# f-91k.net
KiCad netlist of a schematic drawn in EAGLE
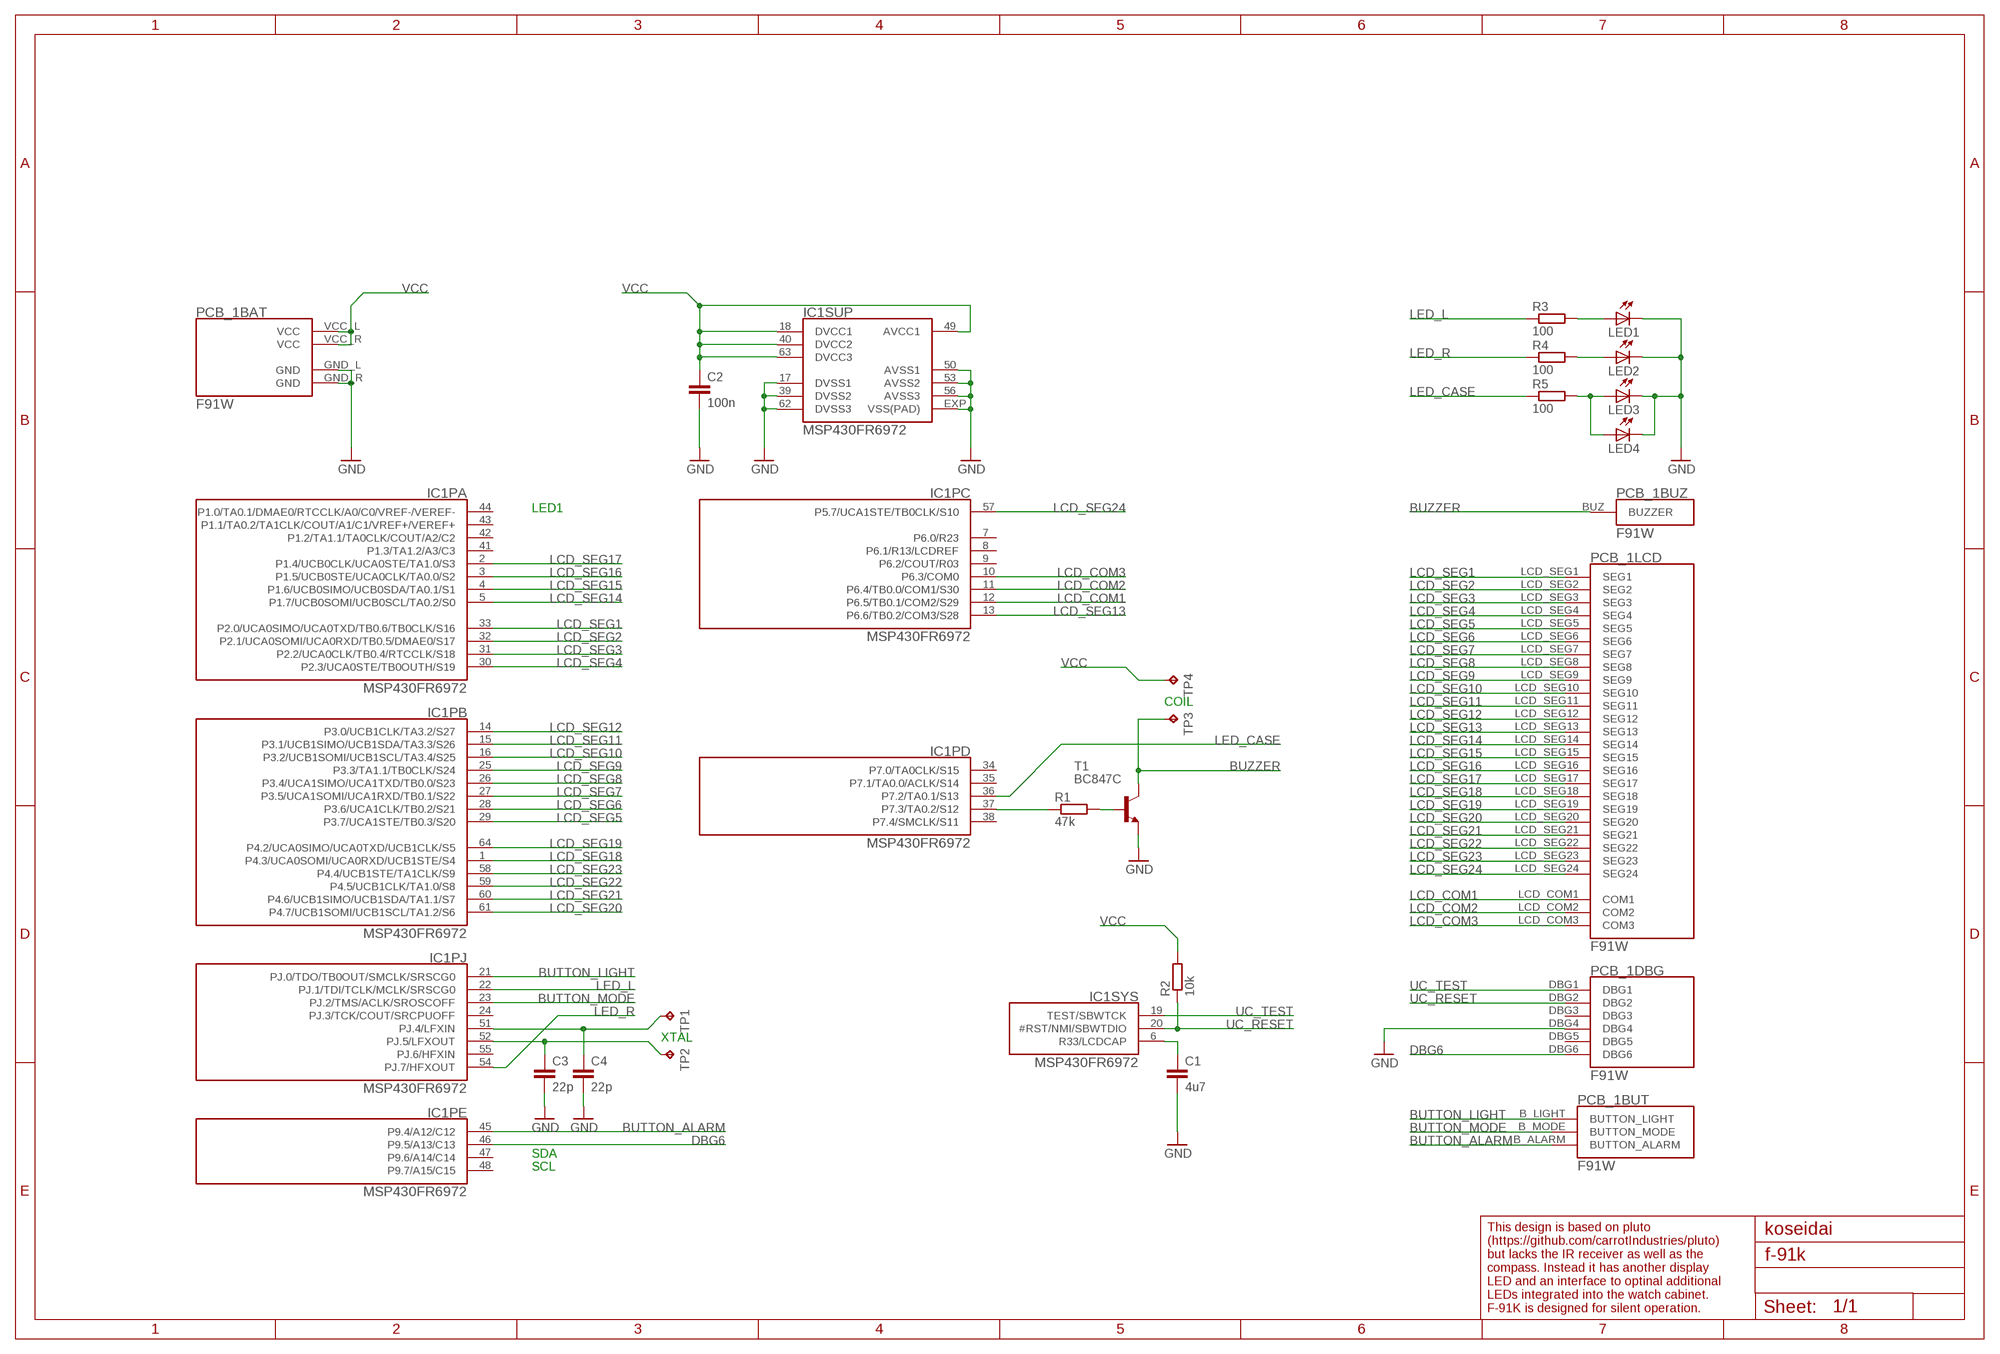
[diagram p0: schematic, sheet 1]

(export (version "E")
  (design (tool "Eeschema 10.0.6"))
  (components
    (comp (ref "C1")
      (value "4u7")
      (footprint "eagle-import:C0603-WW")
      (libsource (lib "eagle-import") (part "C-EUC0603-WW"))
    )
    (comp (ref "C2")
      (value "100n")
      (footprint "eagle-import:C0603-WW")
      (libsource (lib "eagle-import") (part "C-EUC0603-WW"))
    )
    (comp (ref "C3")
      (value "22p")
      (footprint "eagle-import:C0603-WW")
      (libsource (lib "eagle-import") (part "C-EUC0603-WW"))
    )
    (comp (ref "C4")
      (value "22p")
      (footprint "eagle-import:C0603-WW")
      (libsource (lib "eagle-import") (part "C-EUC0603-WW"))
    )
    (comp (ref "IC1")
      (value "MSP430FR6972")
      (footprint "eagle-import:QFN64-9X9")
      (libsource (lib "eagle-import") (part "MSP430FR6972"))
    )
    (comp (ref "LED1")
      (value "LEDCHIPLED_0805")
      (footprint "eagle-import:CHIPLED_0805")
      (libsource (lib "eagle-import") (part "LEDCHIPLED_0805"))
    )
    (comp (ref "LED2")
      (value "LEDCHIPLED_0805")
      (footprint "eagle-import:CHIPLED_0805")
      (libsource (lib "eagle-import") (part "LEDCHIPLED_0805"))
    )
    (comp (ref "LED3")
      (value "LEDCHIPLED_0603")
      (footprint "eagle-import:CHIPLED_0603")
      (libsource (lib "eagle-import") (part "LEDCHIPLED_0603"))
    )
    (comp (ref "LED4")
      (value "LEDCHIPLED_0603")
      (footprint "eagle-import:CHIPLED_0603")
      (libsource (lib "eagle-import") (part "LEDCHIPLED_0603"))
    )
    (comp (ref "PCB_1")
      (value "F91W")
      (footprint "eagle-import:F91W")
      (libsource (lib "eagle-import") (part "F91W"))
    )
    (comp (ref "R1")
      (value "47k")
      (footprint "eagle-import:R0603-WW")
      (libsource (lib "eagle-import") (part "R-EU_R0603-WW"))
    )
    (comp (ref "R2")
      (value "10k")
      (footprint "eagle-import:R0603-WW")
      (libsource (lib "eagle-import") (part "R-EU_R0603-WW"))
    )
    (comp (ref "R3")
      (value "100")
      (footprint "eagle-import:R0603-WW")
      (libsource (lib "eagle-import") (part "R-EU_R0603-WW"))
    )
    (comp (ref "R4")
      (value "100")
      (footprint "eagle-import:R0603-WW")
      (libsource (lib "eagle-import") (part "R-EU_R0603-WW"))
    )
    (comp (ref "R5")
      (value "100")
      (footprint "eagle-import:R0603-WW")
      (libsource (lib "eagle-import") (part "R-EU_R0603-WW"))
    )
    (comp (ref "T1")
      (value "BC847C")
      (footprint "eagle-import:SOT23-BEC")
      (libsource (lib "eagle-import") (part "-NPN-SOT23-BECBC847C"))
    )
    (comp (ref "TP1")
      (value "TPTP07SQ")
      (footprint "eagle-import:TP07SQ")
      (libsource (lib "eagle-import") (part "TPTP07SQ"))
    )
    (comp (ref "TP2")
      (value "TPTP07SQ")
      (footprint "eagle-import:TP07SQ")
      (libsource (lib "eagle-import") (part "TPTP07SQ"))
    )
    (comp (ref "TP3")
      (value "TPTP11SQ")
      (footprint "eagle-import:TP11SQ")
      (libsource (lib "eagle-import") (part "TPTP11SQ"))
    )
    (comp (ref "TP4")
      (value "TPTP11SQ")
      (footprint "eagle-import:TP11SQ")
      (libsource (lib "eagle-import") (part "TPTP11SQ"))
    )
  )
  (nets
    (net (code "1") (name "/BUTTON_ALARM") (class "Default")
      (node (ref "IC1") (pin "45") (pinfunction "P9.4/A12/C12_45") (pintype "bidirectional"))
      (node (ref "PCB_1") (pin "B_ALARM") (pinfunction "BUTTON_ALARM_B_ALARM") (pintype "output"))
    )
    (net (code "2") (name "/BUTTON_LIGHT") (class "Default")
      (node (ref "IC1") (pin "21") (pinfunction "PJ.0/TDO/TB0OUT/SMCLK/SRSCG0_21") (pintype "bidirectional"))
      (node (ref "PCB_1") (pin "B_LIGHT") (pinfunction "BUTTON_LIGHT_B_LIGHT") (pintype "output"))
    )
    (net (code "3") (name "/BUTTON_MODE") (class "Default")
      (node (ref "IC1") (pin "23") (pinfunction "PJ.2/TMS/ACLK/SROSCOFF_23") (pintype "bidirectional"))
      (node (ref "PCB_1") (pin "B_MODE") (pinfunction "BUTTON_MODE_B_MODE") (pintype "output"))
    )
    (net (code "4") (name "/BUZZER") (class "Default")
      (node (ref "PCB_1") (pin "BUZ") (pinfunction "BUZZER_BUZ") (pintype "passive"))
      (node (ref "T1") (pin "C") (pinfunction "C_C") (pintype "passive"))
      (node (ref "TP3") (pin "TP") (pinfunction "TP_TP") (pintype "input"))
    )
    (net (code "5") (name "/DBG6") (class "Default")
      (node (ref "IC1") (pin "46") (pinfunction "P9.5/A13/C13_46") (pintype "bidirectional"))
      (node (ref "PCB_1") (pin "DBG6") (pinfunction "DBG6_DBG6") (pintype "bidirectional"))
    )
    (net (code "6") (name "/LCD_COM1") (class "Default")
      (node (ref "IC1") (pin "12") (pinfunction "P6.5/TB0.1/COM2/S29_12") (pintype "bidirectional"))
      (node (ref "PCB_1") (pin "LCD_COM1") (pinfunction "COM1_LCD_COM1") (pintype "input"))
    )
    (net (code "7") (name "/LCD_COM2") (class "Default")
      (node (ref "IC1") (pin "11") (pinfunction "P6.4/TB0.0/COM1/S30_11") (pintype "bidirectional"))
      (node (ref "PCB_1") (pin "LCD_COM2") (pinfunction "COM2_LCD_COM2") (pintype "input"))
    )
    (net (code "8") (name "/LCD_COM3") (class "Default")
      (node (ref "IC1") (pin "10") (pinfunction "P6.3/COM0_10") (pintype "bidirectional"))
      (node (ref "PCB_1") (pin "LCD_COM3") (pinfunction "COM3_LCD_COM3") (pintype "input"))
    )
    (net (code "9") (name "/LCD_SEG1") (class "Default")
      (node (ref "IC1") (pin "33") (pinfunction "P2.0/UCA0SIMO/UCA0TXD/TB0.6/TB0CLK/S16_33") (pintype "bidirectional"))
      (node (ref "PCB_1") (pin "LCD_SEG1") (pinfunction "SEG1_LCD_SEG1") (pintype "input"))
    )
    (net (code "10") (name "/LCD_SEG2") (class "Default")
      (node (ref "IC1") (pin "32") (pinfunction "P2.1/UCA0SOMI/UCA0RXD/TB0.5/DMAE0/S17_32") (pintype "bidirectional"))
      (node (ref "PCB_1") (pin "LCD_SEG2") (pinfunction "SEG2_LCD_SEG2") (pintype "input"))
    )
    (net (code "11") (name "/LCD_SEG3") (class "Default")
      (node (ref "IC1") (pin "31") (pinfunction "P2.2/UCA0CLK/TB0.4/RTCCLK/S18_31") (pintype "bidirectional"))
      (node (ref "PCB_1") (pin "LCD_SEG3") (pinfunction "SEG3_LCD_SEG3") (pintype "input"))
    )
    (net (code "12") (name "/LCD_SEG4") (class "Default")
      (node (ref "IC1") (pin "30") (pinfunction "P2.3/UCA0STE/TB0OUTH/S19_30") (pintype "bidirectional"))
      (node (ref "PCB_1") (pin "LCD_SEG4") (pinfunction "SEG4_LCD_SEG4") (pintype "input"))
    )
    (net (code "13") (name "/LCD_SEG5") (class "Default")
      (node (ref "IC1") (pin "29") (pinfunction "P3.7/UCA1STE/TB0.3/S20_29") (pintype "bidirectional"))
      (node (ref "PCB_1") (pin "LCD_SEG5") (pinfunction "SEG5_LCD_SEG5") (pintype "input"))
    )
    (net (code "14") (name "/LCD_SEG6") (class "Default")
      (node (ref "IC1") (pin "28") (pinfunction "P3.6/UCA1CLK/TB0.2/S21_28") (pintype "bidirectional"))
      (node (ref "PCB_1") (pin "LCD_SEG6") (pinfunction "SEG6_LCD_SEG6") (pintype "input"))
    )
    (net (code "15") (name "/LCD_SEG7") (class "Default")
      (node (ref "IC1") (pin "27") (pinfunction "P3.5/UCA1SOMI/UCA1RXD/TB0.1/S22_27") (pintype "bidirectional"))
      (node (ref "PCB_1") (pin "LCD_SEG7") (pinfunction "SEG7_LCD_SEG7") (pintype "input"))
    )
    (net (code "16") (name "/LCD_SEG8") (class "Default")
      (node (ref "IC1") (pin "26") (pinfunction "P3.4/UCA1SIMO/UCA1TXD/TB0.0/S23_26") (pintype "bidirectional"))
      (node (ref "PCB_1") (pin "LCD_SEG8") (pinfunction "SEG8_LCD_SEG8") (pintype "input"))
    )
    (net (code "17") (name "/LCD_SEG9") (class "Default")
      (node (ref "IC1") (pin "25") (pinfunction "P3.3/TA1.1/TB0CLK/S24_25") (pintype "bidirectional"))
      (node (ref "PCB_1") (pin "LCD_SEG9") (pinfunction "SEG9_LCD_SEG9") (pintype "input"))
    )
    (net (code "18") (name "/LCD_SEG10") (class "Default")
      (node (ref "IC1") (pin "16") (pinfunction "P3.2/UCB1SOMI/UCB1SCL/TA3.4/S25_16") (pintype "bidirectional"))
      (node (ref "PCB_1") (pin "LCD_SEG10") (pinfunction "SEG10_LCD_SEG10") (pintype "input"))
    )
    (net (code "19") (name "/LCD_SEG11") (class "Default")
      (node (ref "IC1") (pin "15") (pinfunction "P3.1/UCB1SIMO/UCB1SDA/TA3.3/S26_15") (pintype "bidirectional"))
      (node (ref "PCB_1") (pin "LCD_SEG11") (pinfunction "SEG11_LCD_SEG11") (pintype "input"))
    )
    (net (code "20") (name "/LCD_SEG12") (class "Default")
      (node (ref "IC1") (pin "14") (pinfunction "P3.0/UCB1CLK/TA3.2/S27_14") (pintype "bidirectional"))
      (node (ref "PCB_1") (pin "LCD_SEG12") (pinfunction "SEG12_LCD_SEG12") (pintype "input"))
    )
    (net (code "21") (name "/LCD_SEG13") (class "Default")
      (node (ref "IC1") (pin "13") (pinfunction "P6.6/TB0.2/COM3/S28_13") (pintype "bidirectional"))
      (node (ref "PCB_1") (pin "LCD_SEG13") (pinfunction "SEG13_LCD_SEG13") (pintype "input"))
    )
    (net (code "22") (name "/LCD_SEG14") (class "Default")
      (node (ref "IC1") (pin "5") (pinfunction "P1.7/UCB0SOMI/UCB0SCL/TA0.2/S0_5") (pintype "bidirectional"))
      (node (ref "PCB_1") (pin "LCD_SEG14") (pinfunction "SEG14_LCD_SEG14") (pintype "input"))
    )
    (net (code "23") (name "/LCD_SEG15") (class "Default")
      (node (ref "IC1") (pin "4") (pinfunction "P1.6/UCB0SIMO/UCB0SDA/TA0.1/S1_4") (pintype "bidirectional"))
      (node (ref "PCB_1") (pin "LCD_SEG15") (pinfunction "SEG15_LCD_SEG15") (pintype "input"))
    )
    (net (code "24") (name "/LCD_SEG16") (class "Default")
      (node (ref "IC1") (pin "3") (pinfunction "P1.5/UCB0STE/UCA0CLK/TA0.0/S2_3") (pintype "bidirectional"))
      (node (ref "PCB_1") (pin "LCD_SEG16") (pinfunction "SEG16_LCD_SEG16") (pintype "input"))
    )
    (net (code "25") (name "/LCD_SEG17") (class "Default")
      (node (ref "IC1") (pin "2") (pinfunction "P1.4/UCB0CLK/UCA0STE/TA1.0/S3_2") (pintype "bidirectional"))
      (node (ref "PCB_1") (pin "LCD_SEG17") (pinfunction "SEG17_LCD_SEG17") (pintype "input"))
    )
    (net (code "26") (name "/LCD_SEG18") (class "Default")
      (node (ref "IC1") (pin "1") (pinfunction "P4.3/UCA0SOMI/UCA0RXD/UCB1STE/S4_1") (pintype "bidirectional"))
      (node (ref "PCB_1") (pin "LCD_SEG18") (pinfunction "SEG18_LCD_SEG18") (pintype "input"))
    )
    (net (code "27") (name "/LCD_SEG19") (class "Default")
      (node (ref "IC1") (pin "64") (pinfunction "P4.2/UCA0SIMO/UCA0TXD/UCB1CLK/S5_64") (pintype "bidirectional"))
      (node (ref "PCB_1") (pin "LCD_SEG19") (pinfunction "SEG19_LCD_SEG19") (pintype "input"))
    )
    (net (code "28") (name "/LCD_SEG20") (class "Default")
      (node (ref "IC1") (pin "61") (pinfunction "P4.7/UCB1SOMI/UCB1SCL/TA1.2/S6_61") (pintype "bidirectional"))
      (node (ref "PCB_1") (pin "LCD_SEG20") (pinfunction "SEG20_LCD_SEG20") (pintype "input"))
    )
    (net (code "29") (name "/LCD_SEG21") (class "Default")
      (node (ref "IC1") (pin "60") (pinfunction "P4.6/UCB1SIMO/UCB1SDA/TA1.1/S7_60") (pintype "bidirectional"))
      (node (ref "PCB_1") (pin "LCD_SEG21") (pinfunction "SEG21_LCD_SEG21") (pintype "input"))
    )
    (net (code "30") (name "/LCD_SEG22") (class "Default")
      (node (ref "IC1") (pin "59") (pinfunction "P4.5/UCB1CLK/TA1.0/S8_59") (pintype "bidirectional"))
      (node (ref "PCB_1") (pin "LCD_SEG22") (pinfunction "SEG22_LCD_SEG22") (pintype "input"))
    )
    (net (code "31") (name "/LCD_SEG23") (class "Default")
      (node (ref "IC1") (pin "58") (pinfunction "P4.4/UCB1STE/TA1CLK/S9_58") (pintype "bidirectional"))
      (node (ref "PCB_1") (pin "LCD_SEG23") (pinfunction "SEG23_LCD_SEG23") (pintype "input"))
    )
    (net (code "32") (name "/LCD_SEG24") (class "Default")
      (node (ref "IC1") (pin "57") (pinfunction "P5.7/UCA1STE/TB0CLK/S10_57") (pintype "bidirectional"))
      (node (ref "PCB_1") (pin "LCD_SEG24") (pinfunction "SEG24_LCD_SEG24") (pintype "input"))
    )
    (net (code "33") (name "/LED_CASE") (class "Default")
      (node (ref "IC1") (pin "36") (pinfunction "P7.2/TA0.1/S13_36") (pintype "bidirectional"))
      (node (ref "R5") (pin "1") (pinfunction "1_1") (pintype "passive"))
    )
    (net (code "34") (name "/LED_L") (class "Default")
      (node (ref "IC1") (pin "22") (pinfunction "PJ.1/TDI/TCLK/MCLK/SRSCG0_22") (pintype "bidirectional"))
      (node (ref "R3") (pin "1") (pinfunction "1_1") (pintype "passive"))
    )
    (net (code "35") (name "/LED_R") (class "Default")
      (node (ref "IC1") (pin "54") (pinfunction "PJ.7/HFXOUT_54") (pintype "bidirectional"))
      (node (ref "R4") (pin "1") (pinfunction "1_1") (pintype "passive"))
    )
    (net (code "36") (name "/UC_RESET") (class "Default")
      (node (ref "IC1") (pin "20") (pinfunction "#RST/NMI/SBWTDIO_20") (pintype "bidirectional"))
      (node (ref "PCB_1") (pin "DBG2") (pinfunction "DBG2_DBG2") (pintype "bidirectional"))
      (node (ref "R2") (pin "1") (pinfunction "1_1") (pintype "passive"))
    )
    (net (code "37") (name "/UC_TEST") (class "Default")
      (node (ref "IC1") (pin "19") (pinfunction "TEST/SBWTCK_19") (pintype "bidirectional"))
      (node (ref "PCB_1") (pin "DBG1") (pinfunction "DBG1_DBG1") (pintype "bidirectional"))
    )
    (net (code "38") (name "/VCC") (class "Default")
      (node (ref "C2") (pin "1") (pinfunction "1_1") (pintype "passive"))
      (node (ref "IC1") (pin "18") (pinfunction "DVCC1_18") (pintype "bidirectional"))
      (node (ref "IC1") (pin "40") (pinfunction "DVCC2_40") (pintype "bidirectional"))
      (node (ref "IC1") (pin "49") (pinfunction "AVCC1_49") (pintype "bidirectional"))
      (node (ref "IC1") (pin "63") (pinfunction "DVCC3_63") (pintype "bidirectional"))
      (node (ref "PCB_1") (pin "VCC_L") (pinfunction "VCC_VCC_L") (pintype "power_in"))
      (node (ref "PCB_1") (pin "VCC_R") (pinfunction "VCC_VCC_R") (pintype "power_in"))
      (node (ref "R2") (pin "2") (pinfunction "2_2") (pintype "passive"))
      (node (ref "TP4") (pin "TP") (pinfunction "TP_TP") (pintype "input"))
    )
    (net (code "39") (name "GND") (class "Default")
      (node (ref "C1") (pin "2") (pinfunction "2_2") (pintype "passive"))
      (node (ref "C2") (pin "2") (pinfunction "2_2") (pintype "passive"))
      (node (ref "C3") (pin "2") (pinfunction "2_2") (pintype "passive"))
      (node (ref "C4") (pin "2") (pinfunction "2_2") (pintype "passive"))
      (node (ref "IC1") (pin "17") (pinfunction "DVSS1_17") (pintype "bidirectional"))
      (node (ref "IC1") (pin "39") (pinfunction "DVSS2_39") (pintype "bidirectional"))
      (node (ref "IC1") (pin "50") (pinfunction "AVSS1_50") (pintype "bidirectional"))
      (node (ref "IC1") (pin "53") (pinfunction "AVSS2_53") (pintype "bidirectional"))
      (node (ref "IC1") (pin "56") (pinfunction "AVSS3_56") (pintype "bidirectional"))
      (node (ref "IC1") (pin "62") (pinfunction "DVSS3_62") (pintype "bidirectional"))
      (node (ref "IC1") (pin "EXP") (pinfunction "VSS(PAD)_EXP") (pintype "bidirectional"))
      (node (ref "LED1") (pin "C") (pinfunction "C_C") (pintype "passive"))
      (node (ref "LED2") (pin "C") (pinfunction "C_C") (pintype "passive"))
      (node (ref "LED3") (pin "C") (pinfunction "C_C") (pintype "passive"))
      (node (ref "LED4") (pin "C") (pinfunction "C_C") (pintype "passive"))
      (node (ref "PCB_1") (pin "DBG4") (pinfunction "DBG4_DBG4") (pintype "bidirectional"))
      (node (ref "PCB_1") (pin "GND_L") (pinfunction "GND_GND_L") (pintype "power_in"))
      (node (ref "PCB_1") (pin "GND_R") (pinfunction "GND_GND_R") (pintype "power_in"))
      (node (ref "T1") (pin "E") (pinfunction "E_E") (pintype "passive"))
    )
    (net (code "40") (name "Net-(IC1D-P7.3{slash}TA0.2{slash}S12)") (class "Default")
      (node (ref "IC1") (pin "37") (pinfunction "P7.3/TA0.2/S12_37") (pintype "bidirectional"))
      (node (ref "R1") (pin "1") (pinfunction "1_1") (pintype "passive"))
    )
    (net (code "41") (name "Net-(IC1F-PJ.4{slash}LFXIN)") (class "Default")
      (node (ref "C4") (pin "1") (pinfunction "1_1") (pintype "passive"))
      (node (ref "IC1") (pin "51") (pinfunction "PJ.4/LFXIN_51") (pintype "bidirectional"))
      (node (ref "TP1") (pin "TP") (pinfunction "TP_TP") (pintype "input"))
    )
    (net (code "42") (name "Net-(IC1F-PJ.5{slash}LFXOUT)") (class "Default")
      (node (ref "C3") (pin "1") (pinfunction "1_1") (pintype "passive"))
      (node (ref "IC1") (pin "52") (pinfunction "PJ.5/LFXOUT_52") (pintype "bidirectional"))
      (node (ref "TP2") (pin "TP") (pinfunction "TP_TP") (pintype "input"))
    )
    (net (code "43") (name "Net-(IC1H-R33{slash}LCDCAP)") (class "Default")
      (node (ref "C1") (pin "1") (pinfunction "1_1") (pintype "passive"))
      (node (ref "IC1") (pin "6") (pinfunction "R33/LCDCAP_6") (pintype "bidirectional"))
    )
    (net (code "44") (name "Net-(LED1-PadA)") (class "Default")
      (node (ref "LED1") (pin "A") (pinfunction "A_A") (pintype "passive"))
      (node (ref "R3") (pin "2") (pinfunction "2_2") (pintype "passive"))
    )
    (net (code "45") (name "Net-(LED2-PadA)") (class "Default")
      (node (ref "LED2") (pin "A") (pinfunction "A_A") (pintype "passive"))
      (node (ref "R4") (pin "2") (pinfunction "2_2") (pintype "passive"))
    )
    (net (code "46") (name "Net-(LED3-PadA)") (class "Default")
      (node (ref "LED3") (pin "A") (pinfunction "A_A") (pintype "passive"))
      (node (ref "LED4") (pin "A") (pinfunction "A_A") (pintype "passive"))
      (node (ref "R5") (pin "2") (pinfunction "2_2") (pintype "passive"))
    )
    (net (code "47") (name "Net-(R1-Pad2)") (class "Default")
      (node (ref "R1") (pin "2") (pinfunction "2_2") (pintype "passive"))
      (node (ref "T1") (pin "B") (pinfunction "B_B") (pintype "passive"))
    )
    (net (code "48") (name "unconnected-(IC1A-P1.0{slash}TA0.1{slash}DMAE0{slash}RTCCLK{slash}A0{slash}C0{slash}VREF-{slash}VEREF--Pad44)") (class "Default")
      (node (ref "IC1") (pin "44") (pinfunction "P1.0/TA0.1/DMAE0/RTCCLK/A0/C0/VREF-/VEREF-_44") (pintype "bidirectional"))
    )
    (net (code "49") (name "unconnected-(IC1A-P1.1{slash}TA0.2{slash}TA1CLK{slash}COUT{slash}A1{slash}C1{slash}VREF+{slash}VEREF+-Pad43)") (class "Default")
      (node (ref "IC1") (pin "43") (pinfunction "P1.1/TA0.2/TA1CLK/COUT/A1/C1/VREF+/VEREF+_43") (pintype "bidirectional"))
    )
    (net (code "50") (name "unconnected-(IC1A-P1.2{slash}TA1.1{slash}TA0CLK{slash}COUT{slash}A2{slash}C2-Pad42)") (class "Default")
      (node (ref "IC1") (pin "42") (pinfunction "P1.2/TA1.1/TA0CLK/COUT/A2/C2_42") (pintype "bidirectional"))
    )
    (net (code "51") (name "unconnected-(IC1A-P1.3{slash}TA1.2{slash}A3{slash}C3-Pad41)") (class "Default")
      (node (ref "IC1") (pin "41") (pinfunction "P1.3/TA1.2/A3/C3_41") (pintype "bidirectional"))
    )
    (net (code "52") (name "unconnected-(IC1C-P6.0{slash}R23-Pad7)") (class "Default")
      (node (ref "IC1") (pin "7") (pinfunction "P6.0/R23_7") (pintype "bidirectional"))
    )
    (net (code "53") (name "unconnected-(IC1C-P6.1{slash}R13{slash}LCDREF-Pad8)") (class "Default")
      (node (ref "IC1") (pin "8") (pinfunction "P6.1/R13/LCDREF_8") (pintype "bidirectional"))
    )
    (net (code "54") (name "unconnected-(IC1C-P6.2{slash}COUT{slash}R03-Pad9)") (class "Default")
      (node (ref "IC1") (pin "9") (pinfunction "P6.2/COUT/R03_9") (pintype "bidirectional"))
    )
    (net (code "55") (name "unconnected-(IC1D-P7.0{slash}TA0CLK{slash}S15-Pad34)") (class "Default")
      (node (ref "IC1") (pin "34") (pinfunction "P7.0/TA0CLK/S15_34") (pintype "bidirectional"))
    )
    (net (code "56") (name "unconnected-(IC1D-P7.1{slash}TA0.0{slash}ACLK{slash}S14-Pad35)") (class "Default")
      (node (ref "IC1") (pin "35") (pinfunction "P7.1/TA0.0/ACLK/S14_35") (pintype "bidirectional"))
    )
    (net (code "57") (name "unconnected-(IC1D-P7.4{slash}SMCLK{slash}S11-Pad38)") (class "Default")
      (node (ref "IC1") (pin "38") (pinfunction "P7.4/SMCLK/S11_38") (pintype "bidirectional"))
    )
    (net (code "58") (name "unconnected-(IC1E-P9.6{slash}A14{slash}C14-Pad47)") (class "Default")
      (node (ref "IC1") (pin "47") (pinfunction "P9.6/A14/C14_47") (pintype "bidirectional"))
    )
    (net (code "59") (name "unconnected-(IC1E-P9.7{slash}A15{slash}C15-Pad48)") (class "Default")
      (node (ref "IC1") (pin "48") (pinfunction "P9.7/A15/C15_48") (pintype "bidirectional"))
    )
    (net (code "60") (name "unconnected-(IC1F-PJ.3{slash}TCK{slash}COUT{slash}SRCPUOFF-Pad24)") (class "Default")
      (node (ref "IC1") (pin "24") (pinfunction "PJ.3/TCK/COUT/SRCPUOFF_24") (pintype "bidirectional"))
    )
    (net (code "61") (name "unconnected-(IC1F-PJ.6{slash}HFXIN-Pad55)") (class "Default")
      (node (ref "IC1") (pin "55") (pinfunction "PJ.6/HFXIN_55") (pintype "bidirectional"))
    )
    (net (code "62") (name "unconnected-(PCB_1-PadDBG3)") (class "Default")
      (node (ref "PCB_1") (pin "DBG3") (pinfunction "DBG3_DBG3") (pintype "bidirectional"))
    )
    (net (code "63") (name "unconnected-(PCB_1-PadDBG5)") (class "Default")
      (node (ref "PCB_1") (pin "DBG5") (pinfunction "DBG5_DBG5") (pintype "bidirectional"))
    )
  )
)
